# 20_MIPI_DSI_TX0.net
KiCad netlist of a schematic drawn in Altium Designer
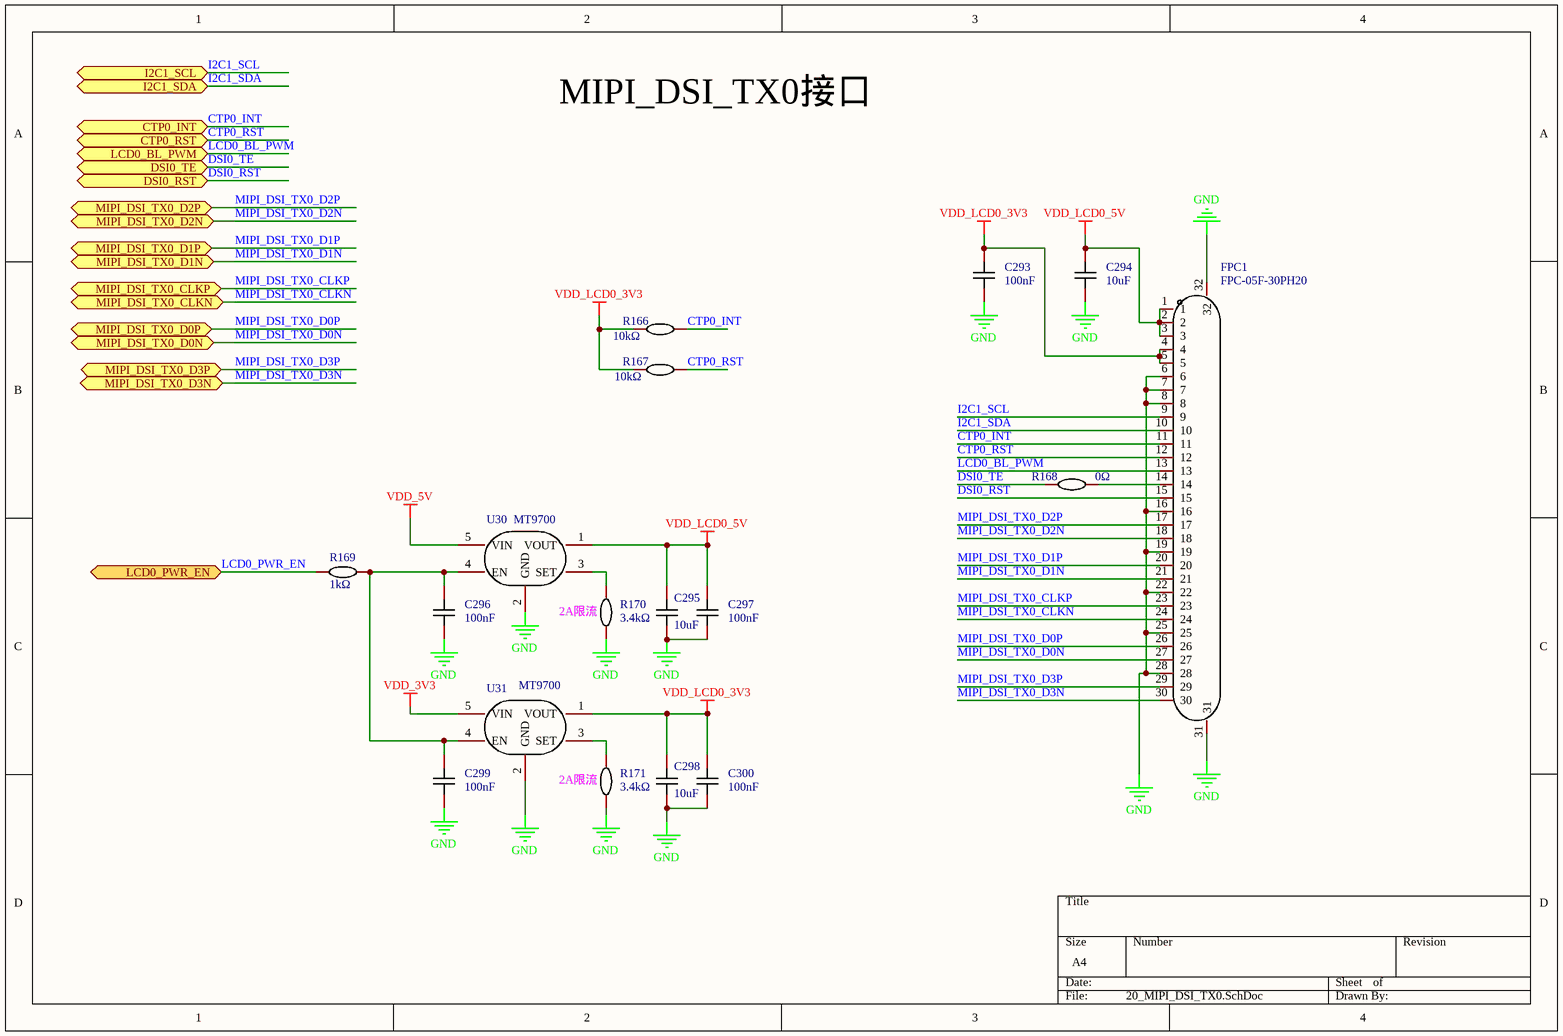
[diagram p0: 20_MIPI_DSI_TX0.SchDoc]

(export (version "E")
  (design (tool "Eeschema 10.0.6"))
  (components
    (comp (ref "C293")
      (value "100nF")
      (footprint "C0603")
      (fields
        (field (name "NAME") "100nF")
        (field (name "MANUFACTURER") "YAGEO(国巨)")
        (field (name "MANUFACTURER PART") "CC0603KRX7R9BB104")
        (field (name "TOLERANCE") "±10%")
      )
      (libsource (lib "altium-import") (part "root_1_CC0603KRX7R9BB104_"))
    )
    (comp (ref "C294")
      (value "10uF")
      (footprint "C0603")
      (fields
        (field (name "NAME") "10uF")
        (field (name "MANUFACTURER") "SAMSUNG(三星)")
        (field (name "MANUFACTURER PART") "CL10A106KP8NNNC")
        (field (name "TOLERANCE") "±10%")
      )
      (libsource (lib "altium-import") (part "root_1_CL10A106KP8NNNC_"))
    )
    (comp (ref "C295")
      (value "10uF")
      (footprint "C0603")
      (fields
        (field (name "NAME") "10uF")
        (field (name "MANUFACTURER") "SAMSUNG(三星)")
        (field (name "MANUFACTURER PART") "CL10A106KP8NNNC")
        (field (name "TOLERANCE") "±10%")
      )
      (libsource (lib "altium-import") (part "root_1_CL10A106KP8NNNC_"))
    )
    (comp (ref "C296")
      (value "100nF")
      (footprint "C0603")
      (fields
        (field (name "NAME") "100nF")
        (field (name "MANUFACTURER") "YAGEO(国巨)")
        (field (name "MANUFACTURER PART") "CC0603KRX7R9BB104")
        (field (name "TOLERANCE") "±10%")
      )
      (libsource (lib "altium-import") (part "root_1_CC0603KRX7R9BB104_"))
    )
    (comp (ref "C297")
      (value "100nF")
      (footprint "C0603")
      (fields
        (field (name "NAME") "100nF")
        (field (name "MANUFACTURER") "YAGEO(国巨)")
        (field (name "MANUFACTURER PART") "CC0603KRX7R9BB104")
        (field (name "TOLERANCE") "±10%")
      )
      (libsource (lib "altium-import") (part "root_1_CC0603KRX7R9BB104_"))
    )
    (comp (ref "C298")
      (value "10uF")
      (footprint "C0603")
      (fields
        (field (name "NAME") "10uF")
        (field (name "MANUFACTURER") "SAMSUNG(三星)")
        (field (name "MANUFACTURER PART") "CL10A106KP8NNNC")
        (field (name "TOLERANCE") "±10%")
      )
      (libsource (lib "altium-import") (part "root_1_CL10A106KP8NNNC_"))
    )
    (comp (ref "C299")
      (value "100nF")
      (footprint "C0603")
      (fields
        (field (name "NAME") "100nF")
        (field (name "MANUFACTURER") "YAGEO(国巨)")
        (field (name "MANUFACTURER PART") "CC0603KRX7R9BB104")
        (field (name "TOLERANCE") "±10%")
      )
      (libsource (lib "altium-import") (part "root_1_CC0603KRX7R9BB104_"))
    )
    (comp (ref "C300")
      (value "100nF")
      (footprint "C0603")
      (fields
        (field (name "NAME") "100nF")
        (field (name "MANUFACTURER") "YAGEO(国巨)")
        (field (name "MANUFACTURER PART") "CC0603KRX7R9BB104")
        (field (name "TOLERANCE") "±10%")
      )
      (libsource (lib "altium-import") (part "root_1_CC0603KRX7R9BB104_"))
    )
    (comp (ref "FPC1")
      (value "FPC-05F-30PH20")
      (footprint "FPC-SMD_30P-P0.50_XUNPU_FPC-05F-30PH20")
      (fields (field (name "NAME") "FPC-05F-30PH20") (field (name "MANUFACTURER") "XUNPU(讯普)"))
      (libsource (lib "altium-import") (part "root_0_FPC-05F-30PH20_"))
    )
    (comp (ref "R166")
      (value "10kΩ")
      (footprint "R0603")
      (fields
        (field (name "NAME") "10kΩ")
        (field (name "MANUFACTURER") "UNI-ROYAL(厚声)")
        (field (name "MANUFACTURER PART") "0603WAF1002T5E")
        (field (name "TOLERANCE") "±1%")
      )
      (libsource (lib "altium-import") (part "root_2_0603WAF1002T5E_"))
    )
    (comp (ref "R167")
      (value "10kΩ")
      (footprint "R0603")
      (fields
        (field (name "NAME") "10kΩ")
        (field (name "MANUFACTURER") "UNI-ROYAL(厚声)")
        (field (name "MANUFACTURER PART") "0603WAF1002T5E")
        (field (name "TOLERANCE") "±1%")
      )
      (libsource (lib "altium-import") (part "root_2_0603WAF1002T5E_"))
    )
    (comp (ref "R168")
      (value "0Ω")
      (footprint "R0603")
      (fields
        (field (name "NAME") "0Ω")
        (field (name "MANUFACTURER") "UNI-ROYAL(厚声)")
        (field (name "MANUFACTURER PART") "0603WAF0000T5E")
        (field (name "TOLERANCE") "±1%")
      )
      (libsource (lib "altium-import") (part "root_0_0603WAF0000T5E_"))
    )
    (comp (ref "R169")
      (value "1kΩ")
      (footprint "R0603")
      (fields
        (field (name "NAME") "1kΩ")
        (field (name "MANUFACTURER") "YAGEO(国巨)")
        (field (name "MANUFACTURER PART") "RC0603FR-071KL")
        (field (name "TOLERANCE") "±1%")
      )
      (libsource (lib "altium-import") (part "root_0_RC0603FR-071KL_"))
    )
    (comp (ref "R170")
      (value "3.4kΩ")
      (footprint "R0603")
      (fields
        (field (name "NAME") "3.4kΩ")
        (field (name "MANUFACTURER") "UNI-ROYAL(厚声)")
        (field (name "MANUFACTURER PART") "0603WAF3401T5E")
        (field (name "TOLERANCE") "±1%")
      )
      (libsource (lib "altium-import") (part "root_1_0603WAF3401T5E_"))
    )
    (comp (ref "R171")
      (value "3.4kΩ")
      (footprint "R0603")
      (fields
        (field (name "NAME") "3.4kΩ")
        (field (name "MANUFACTURER") "UNI-ROYAL(厚声)")
        (field (name "MANUFACTURER PART") "0603WAF3401T5E")
        (field (name "TOLERANCE") "±1%")
      )
      (libsource (lib "altium-import") (part "root_1_0603WAF3401T5E_"))
    )
    (comp (ref "U30")
      (value "MT9700")
      (footprint "SOT-23-5_L3.0-W1.7-P0.95-LS2.8-BR")
      (fields (field (name "NAME") "MT9700") (field (name "MANUFACTURER") "西安航天民芯"))
      (libsource (lib "altium-import") (part "root_0_mirrored_MT9700_"))
    )
    (comp (ref "U31")
      (value "MT9700")
      (footprint "SOT-23-5_L3.0-W1.7-P0.95-LS2.8-BR")
      (fields (field (name "NAME") "MT9700") (field (name "MANUFACTURER") "西安航天民芯"))
      (libsource (lib "altium-import") (part "root_0_mirrored_MT9700_"))
    )
  )
  (nets
    (net (code "1") (name "/CTP0_INT") (class "Default")
      (node (ref "FPC1") (pin "11") (pinfunction "11_11") (pintype "passive"))
      (node (ref "R166") (pin "1") (pinfunction "1_1") (pintype "passive"))
    )
    (net (code "2") (name "/CTP0_RST") (class "Default")
      (node (ref "FPC1") (pin "12") (pinfunction "12_12") (pintype "passive"))
      (node (ref "R167") (pin "1") (pinfunction "1_1") (pintype "passive"))
    )
    (net (code "3") (name "/DSI0_RST") (class "Default")
      (node (ref "FPC1") (pin "15") (pinfunction "15_15") (pintype "passive"))
    )
    (net (code "4") (name "/DSI0_TE") (class "Default")
      (node (ref "R168") (pin "1") (pinfunction "1_1") (pintype "passive"))
    )
    (net (code "5") (name "/I2C1_SCL") (class "Default")
      (node (ref "FPC1") (pin "9") (pinfunction "9_9") (pintype "passive"))
    )
    (net (code "6") (name "/I2C1_SDA") (class "Default")
      (node (ref "FPC1") (pin "10") (pinfunction "10_10") (pintype "passive"))
    )
    (net (code "7") (name "/LCD0_BL_PWM") (class "Default")
      (node (ref "FPC1") (pin "13") (pinfunction "13_13") (pintype "passive"))
    )
    (net (code "8") (name "/LCD0_PWR_EN") (class "Default")
      (node (ref "R169") (pin "1") (pinfunction "1_1") (pintype "passive"))
    )
    (net (code "9") (name "/MIPI_DSI_TX0_CLKN") (class "Default")
      (node (ref "FPC1") (pin "24") (pinfunction "24_24") (pintype "passive"))
    )
    (net (code "10") (name "/MIPI_DSI_TX0_CLKP") (class "Default")
      (node (ref "FPC1") (pin "23") (pinfunction "23_23") (pintype "passive"))
    )
    (net (code "11") (name "/MIPI_DSI_TX0_D0N") (class "Default")
      (node (ref "FPC1") (pin "27") (pinfunction "27_27") (pintype "passive"))
    )
    (net (code "12") (name "/MIPI_DSI_TX0_D0P") (class "Default")
      (node (ref "FPC1") (pin "26") (pinfunction "26_26") (pintype "passive"))
    )
    (net (code "13") (name "/MIPI_DSI_TX0_D1N") (class "Default")
      (node (ref "FPC1") (pin "21") (pinfunction "21_21") (pintype "passive"))
    )
    (net (code "14") (name "/MIPI_DSI_TX0_D1P") (class "Default")
      (node (ref "FPC1") (pin "20") (pinfunction "20_20") (pintype "passive"))
    )
    (net (code "15") (name "/MIPI_DSI_TX0_D2N") (class "Default")
      (node (ref "FPC1") (pin "18") (pinfunction "18_18") (pintype "passive"))
    )
    (net (code "16") (name "/MIPI_DSI_TX0_D2P") (class "Default")
      (node (ref "FPC1") (pin "17") (pinfunction "17_17") (pintype "passive"))
    )
    (net (code "17") (name "/MIPI_DSI_TX0_D3N") (class "Default")
      (node (ref "FPC1") (pin "30") (pinfunction "30_30") (pintype "passive"))
    )
    (net (code "18") (name "/MIPI_DSI_TX0_D3P") (class "Default")
      (node (ref "FPC1") (pin "29") (pinfunction "29_29") (pintype "passive"))
    )
    (net (code "19") (name "GND") (class "Default")
      (node (ref "C293") (pin "1") (pinfunction "1_1") (pintype "passive"))
      (node (ref "C294") (pin "1") (pinfunction "1_1") (pintype "passive"))
      (node (ref "C295") (pin "1") (pinfunction "1_1") (pintype "passive"))
      (node (ref "C296") (pin "1") (pinfunction "1_1") (pintype "passive"))
      (node (ref "C297") (pin "1") (pinfunction "1_1") (pintype "passive"))
      (node (ref "C298") (pin "1") (pinfunction "1_1") (pintype "passive"))
      (node (ref "C299") (pin "1") (pinfunction "1_1") (pintype "passive"))
      (node (ref "C300") (pin "1") (pinfunction "1_1") (pintype "passive"))
      (node (ref "FPC1") (pin "16") (pinfunction "16_16") (pintype "passive"))
      (node (ref "FPC1") (pin "19") (pinfunction "19_19") (pintype "passive"))
      (node (ref "FPC1") (pin "22") (pinfunction "22_22") (pintype "passive"))
      (node (ref "FPC1") (pin "25") (pinfunction "25_25") (pintype "passive"))
      (node (ref "FPC1") (pin "28") (pinfunction "28_28") (pintype "passive"))
      (node (ref "FPC1") (pin "31") (pinfunction "31_31") (pintype "passive"))
      (node (ref "FPC1") (pin "32") (pinfunction "32_32") (pintype "passive"))
      (node (ref "FPC1") (pin "6") (pinfunction "6_6") (pintype "passive"))
      (node (ref "FPC1") (pin "7") (pinfunction "7_7") (pintype "passive"))
      (node (ref "FPC1") (pin "8") (pinfunction "8_8") (pintype "passive"))
      (node (ref "R170") (pin "1") (pinfunction "1_1") (pintype "passive"))
      (node (ref "R171") (pin "1") (pinfunction "1_1") (pintype "passive"))
      (node (ref "U30") (pin "2") (pinfunction "GND_2") (pintype "passive"))
      (node (ref "U31") (pin "2") (pinfunction "GND_2") (pintype "passive"))
    )
    (net (code "20") (name "Net-(FPC1-Pad14)") (class "Default")
      (node (ref "FPC1") (pin "14") (pinfunction "14_14") (pintype "passive"))
      (node (ref "R168") (pin "2") (pinfunction "2_2") (pintype "passive"))
    )
    (net (code "21") (name "Net-(U30-EN)") (class "Default")
      (node (ref "C296") (pin "2") (pinfunction "2_2") (pintype "passive"))
      (node (ref "C299") (pin "2") (pinfunction "2_2") (pintype "passive"))
      (node (ref "R169") (pin "2") (pinfunction "2_2") (pintype "passive"))
      (node (ref "U30") (pin "4") (pinfunction "EN_4") (pintype "passive"))
      (node (ref "U31") (pin "4") (pinfunction "EN_4") (pintype "passive"))
    )
    (net (code "22") (name "Net-(U30-SET)") (class "Default")
      (node (ref "R170") (pin "2") (pinfunction "2_2") (pintype "passive"))
      (node (ref "U30") (pin "3") (pinfunction "SET_3") (pintype "passive"))
    )
    (net (code "23") (name "Net-(U31-SET)") (class "Default")
      (node (ref "R171") (pin "2") (pinfunction "2_2") (pintype "passive"))
      (node (ref "U31") (pin "3") (pinfunction "SET_3") (pintype "passive"))
    )
    (net (code "24") (name "VDD_3V3") (class "Default")
      (node (ref "U31") (pin "5") (pinfunction "VIN_5") (pintype "passive"))
    )
    (net (code "25") (name "VDD_5V") (class "Default")
      (node (ref "U30") (pin "5") (pinfunction "VIN_5") (pintype "passive"))
    )
    (net (code "26") (name "VDD_LCD0_3V3") (class "Default")
      (node (ref "C293") (pin "2") (pinfunction "2_2") (pintype "passive"))
      (node (ref "C298") (pin "2") (pinfunction "2_2") (pintype "passive"))
      (node (ref "C300") (pin "2") (pinfunction "2_2") (pintype "passive"))
      (node (ref "FPC1") (pin "4") (pinfunction "4_4") (pintype "passive"))
      (node (ref "FPC1") (pin "5") (pinfunction "5_5") (pintype "passive"))
      (node (ref "R166") (pin "2") (pinfunction "2_2") (pintype "passive"))
      (node (ref "R167") (pin "2") (pinfunction "2_2") (pintype "passive"))
      (node (ref "U31") (pin "1") (pinfunction "VOUT_1") (pintype "passive"))
    )
    (net (code "27") (name "VDD_LCD0_5V") (class "Default")
      (node (ref "C294") (pin "2") (pinfunction "2_2") (pintype "passive"))
      (node (ref "C295") (pin "2") (pinfunction "2_2") (pintype "passive"))
      (node (ref "C297") (pin "2") (pinfunction "2_2") (pintype "passive"))
      (node (ref "FPC1") (pin "1") (pinfunction "1_1") (pintype "passive"))
      (node (ref "FPC1") (pin "2") (pinfunction "2_2") (pintype "passive"))
      (node (ref "FPC1") (pin "3") (pinfunction "3_3") (pintype "passive"))
      (node (ref "U30") (pin "1") (pinfunction "VOUT_1") (pintype "passive"))
    )
  )
)
